# blinkm_mk2c.net
KiCad netlist of a schematic drawn in EAGLE
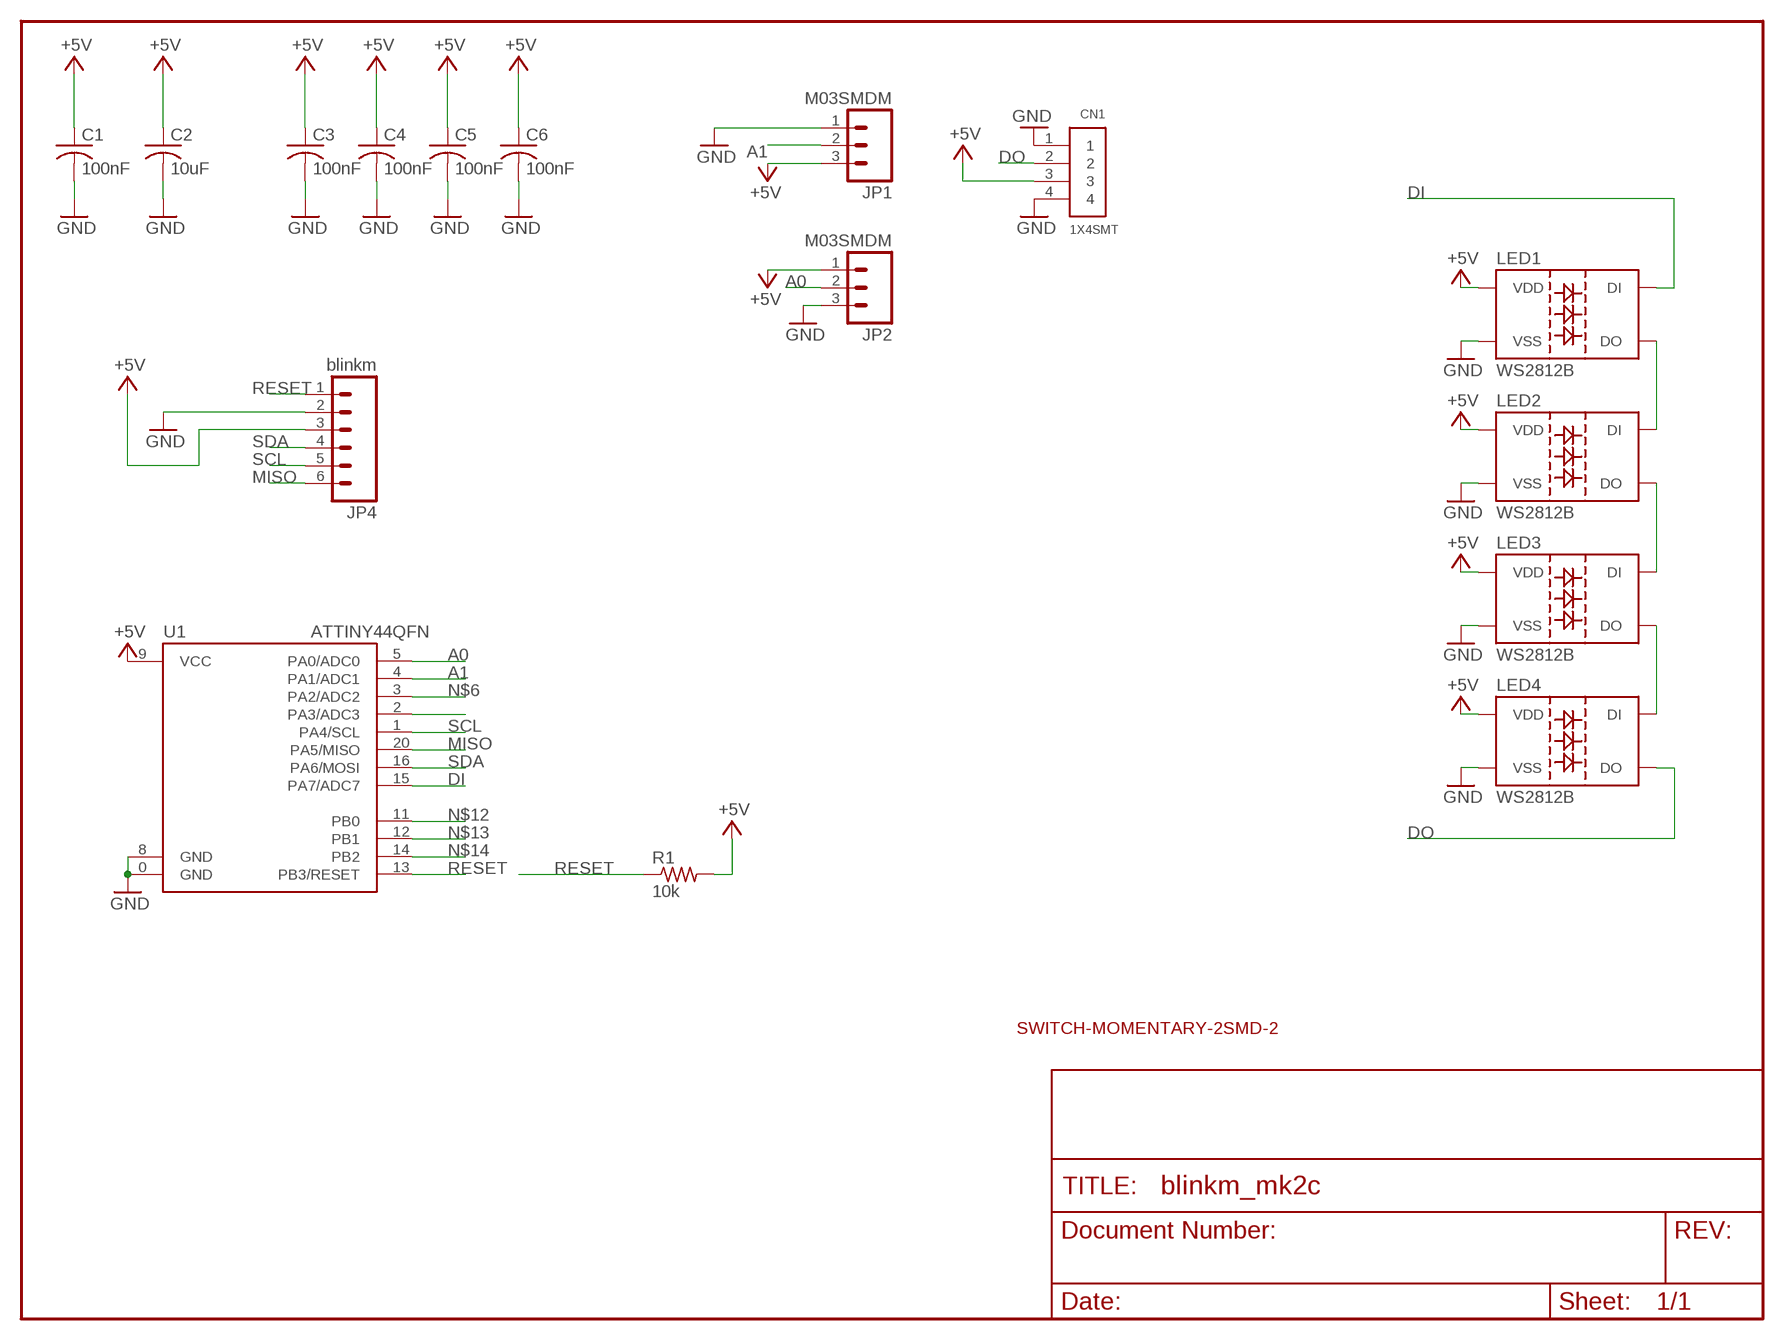
[diagram p0: schematic, sheet 1]

(export (version "E")
  (design (tool "Eeschema 10.0.6"))
  (components
    (comp (ref "C1")
      (value "100nF")
      (footprint "eagle-import:C0603")
      (libsource (lib "eagle-import") (part "C-USC0603"))
    )
    (comp (ref "C2")
      (value "10uF")
      (footprint "eagle-import:C0603")
      (libsource (lib "eagle-import") (part "C-USC0603"))
    )
    (comp (ref "C3")
      (value "100nF")
      (footprint "eagle-import:C0603")
      (libsource (lib "eagle-import") (part "C-USC0603"))
    )
    (comp (ref "C4")
      (value "100nF")
      (footprint "eagle-import:C0603")
      (libsource (lib "eagle-import") (part "C-USC0603"))
    )
    (comp (ref "C5")
      (value "100nF")
      (footprint "eagle-import:C0603")
      (libsource (lib "eagle-import") (part "C-USC0603"))
    )
    (comp (ref "C6")
      (value "100nF")
      (footprint "eagle-import:C0603")
      (libsource (lib "eagle-import") (part "C-USC0603"))
    )
    (comp (ref "CN1")
      (value "1X4SMT")
      (footprint "eagle-import:1X4-SMT")
      (libsource (lib "eagle-import") (part "1X4SMT"))
    )
    (comp (ref "JP1")
      (value "M03SMDM")
      (footprint "eagle-import:1X03-SMD-MINIMAL")
      (libsource (lib "eagle-import") (part "M03SMDM"))
    )
    (comp (ref "JP2")
      (value "M03SMDM")
      (footprint "eagle-import:1X03-SMD-MINIMAL")
      (libsource (lib "eagle-import") (part "M03SMDM"))
    )
    (comp (ref "JP4")
      (value "blinkm")
      (footprint "eagle-import:1X06_LOCK")
      (libsource (lib "eagle-import") (part "M06LOCK"))
    )
    (comp (ref "LED1")
      (value "WS2812B")
      (footprint "eagle-import:WS2812B")
      (libsource (lib "eagle-import") (part "WS2812B"))
    )
    (comp (ref "LED2")
      (value "WS2812B")
      (footprint "eagle-import:WS2812B")
      (libsource (lib "eagle-import") (part "WS2812B"))
    )
    (comp (ref "LED3")
      (value "WS2812B")
      (footprint "eagle-import:WS2812B")
      (libsource (lib "eagle-import") (part "WS2812B"))
    )
    (comp (ref "LED4")
      (value "WS2812B")
      (footprint "eagle-import:WS2812B")
      (libsource (lib "eagle-import") (part "WS2812B"))
    )
    (comp (ref "R1")
      (value "10k")
      (footprint "eagle-import:R0603")
      (libsource (lib "eagle-import") (part "R-US_R0603"))
    )
    (comp (ref "U1")
      (value "ATTINY44QFN")
      (footprint "eagle-import:QFN20")
      (libsource (lib "eagle-import") (part "ATTINY24QFN"))
    )
  )
  (nets
    (net (code "1") (name "+5V") (class "Default")
      (node (ref "C1") (pin "1") (pinfunction "1_1") (pintype "passive"))
      (node (ref "C2") (pin "1") (pinfunction "1_1") (pintype "passive"))
      (node (ref "C3") (pin "1") (pinfunction "1_1") (pintype "passive"))
      (node (ref "C4") (pin "1") (pinfunction "1_1") (pintype "passive"))
      (node (ref "C5") (pin "1") (pinfunction "1_1") (pintype "passive"))
      (node (ref "C6") (pin "1") (pinfunction "1_1") (pintype "passive"))
      (node (ref "CN1") (pin "3") (pinfunction "3_3") (pintype "bidirectional"))
      (node (ref "JP1") (pin "3") (pinfunction "3_3") (pintype "passive"))
      (node (ref "JP2") (pin "1") (pinfunction "1_1") (pintype "passive"))
      (node (ref "JP4") (pin "3") (pinfunction "3_3") (pintype "passive"))
      (node (ref "LED1") (pin "1") (pinfunction "VDD_1") (pintype "bidirectional"))
      (node (ref "LED2") (pin "1") (pinfunction "VDD_1") (pintype "bidirectional"))
      (node (ref "LED3") (pin "1") (pinfunction "VDD_1") (pintype "bidirectional"))
      (node (ref "LED4") (pin "1") (pinfunction "VDD_1") (pintype "bidirectional"))
      (node (ref "R1") (pin "2") (pinfunction "2_2") (pintype "passive"))
      (node (ref "U1") (pin "9") (pinfunction "VCC_9") (pintype "bidirectional"))
    )
    (net (code "2") (name "/A0") (class "Default")
      (node (ref "JP2") (pin "2") (pinfunction "2_2") (pintype "passive"))
      (node (ref "U1") (pin "5") (pinfunction "PA0/ADC0_5") (pintype "bidirectional"))
    )
    (net (code "3") (name "/A1") (class "Default")
      (node (ref "JP1") (pin "2") (pinfunction "2_2") (pintype "passive"))
      (node (ref "U1") (pin "4") (pinfunction "PA1/ADC1_4") (pintype "bidirectional"))
    )
    (net (code "4") (name "/DI") (class "Default")
      (node (ref "LED1") (pin "4") (pinfunction "DI_4") (pintype "bidirectional"))
      (node (ref "U1") (pin "15") (pinfunction "PA7/ADC7_15") (pintype "bidirectional"))
    )
    (net (code "5") (name "/DO") (class "Default")
      (node (ref "CN1") (pin "2") (pinfunction "2_2") (pintype "bidirectional"))
      (node (ref "LED4") (pin "2") (pinfunction "DO_2") (pintype "bidirectional"))
    )
    (net (code "6") (name "/MISO") (class "Default")
      (node (ref "JP4") (pin "6") (pinfunction "6_6") (pintype "passive"))
      (node (ref "U1") (pin "20") (pinfunction "PA5/MISO_20") (pintype "bidirectional"))
    )
    (net (code "7") (name "/N$6") (class "Default")
      (node (ref "U1") (pin "3") (pinfunction "PA2/ADC2_3") (pintype "bidirectional"))
    )
    (net (code "8") (name "/N$12") (class "Default")
      (node (ref "U1") (pin "11") (pinfunction "PB0_11") (pintype "bidirectional"))
    )
    (net (code "9") (name "/N$13") (class "Default")
      (node (ref "U1") (pin "12") (pinfunction "PB1_12") (pintype "bidirectional"))
    )
    (net (code "10") (name "/N$14") (class "Default")
      (node (ref "U1") (pin "14") (pinfunction "PB2_14") (pintype "bidirectional"))
    )
    (net (code "11") (name "/RESET") (class "Default")
      (node (ref "JP4") (pin "1") (pinfunction "1_1") (pintype "passive"))
      (node (ref "R1") (pin "1") (pinfunction "1_1") (pintype "passive"))
      (node (ref "U1") (pin "13") (pinfunction "PB3/RESET_13") (pintype "bidirectional"))
    )
    (net (code "12") (name "/SCL") (class "Default")
      (node (ref "JP4") (pin "5") (pinfunction "5_5") (pintype "passive"))
      (node (ref "U1") (pin "1") (pinfunction "PA4/SCL_1") (pintype "bidirectional"))
    )
    (net (code "13") (name "/SDA") (class "Default")
      (node (ref "JP4") (pin "4") (pinfunction "4_4") (pintype "passive"))
      (node (ref "U1") (pin "16") (pinfunction "PA6/MOSI_16") (pintype "bidirectional"))
    )
    (net (code "14") (name "GND") (class "Default")
      (node (ref "C1") (pin "2") (pinfunction "2_2") (pintype "passive"))
      (node (ref "C2") (pin "2") (pinfunction "2_2") (pintype "passive"))
      (node (ref "C3") (pin "2") (pinfunction "2_2") (pintype "passive"))
      (node (ref "C4") (pin "2") (pinfunction "2_2") (pintype "passive"))
      (node (ref "C5") (pin "2") (pinfunction "2_2") (pintype "passive"))
      (node (ref "C6") (pin "2") (pinfunction "2_2") (pintype "passive"))
      (node (ref "CN1") (pin "1") (pinfunction "1_1") (pintype "bidirectional"))
      (node (ref "CN1") (pin "4") (pinfunction "4_4") (pintype "bidirectional"))
      (node (ref "JP1") (pin "1") (pinfunction "1_1") (pintype "passive"))
      (node (ref "JP2") (pin "3") (pinfunction "3_3") (pintype "passive"))
      (node (ref "JP4") (pin "2") (pinfunction "2_2") (pintype "passive"))
      (node (ref "LED1") (pin "3") (pinfunction "VSS_3") (pintype "bidirectional"))
      (node (ref "LED2") (pin "3") (pinfunction "VSS_3") (pintype "bidirectional"))
      (node (ref "LED3") (pin "3") (pinfunction "VSS_3") (pintype "bidirectional"))
      (node (ref "LED4") (pin "3") (pinfunction "VSS_3") (pintype "bidirectional"))
      (node (ref "U1") (pin "0") (pinfunction "GND_0") (pintype "bidirectional"))
      (node (ref "U1") (pin "8") (pinfunction "GND_8") (pintype "bidirectional"))
    )
    (net (code "15") (name "Net-(LED1-DO)") (class "Default")
      (node (ref "LED1") (pin "2") (pinfunction "DO_2") (pintype "bidirectional"))
      (node (ref "LED2") (pin "4") (pinfunction "DI_4") (pintype "bidirectional"))
    )
    (net (code "16") (name "Net-(LED2-DO)") (class "Default")
      (node (ref "LED2") (pin "2") (pinfunction "DO_2") (pintype "bidirectional"))
      (node (ref "LED3") (pin "4") (pinfunction "DI_4") (pintype "bidirectional"))
    )
    (net (code "17") (name "Net-(LED3-DO)") (class "Default")
      (node (ref "LED3") (pin "2") (pinfunction "DO_2") (pintype "bidirectional"))
      (node (ref "LED4") (pin "4") (pinfunction "DI_4") (pintype "bidirectional"))
    )
    (net (code "18") (name "unconnected-(U1-PA3{slash}ADC3-Pad2)") (class "Default")
      (node (ref "U1") (pin "2") (pinfunction "PA3/ADC3_2") (pintype "bidirectional"))
    )
  )
)
